# Sheet3.net
KiCad netlist of a schematic drawn in Altium Designer
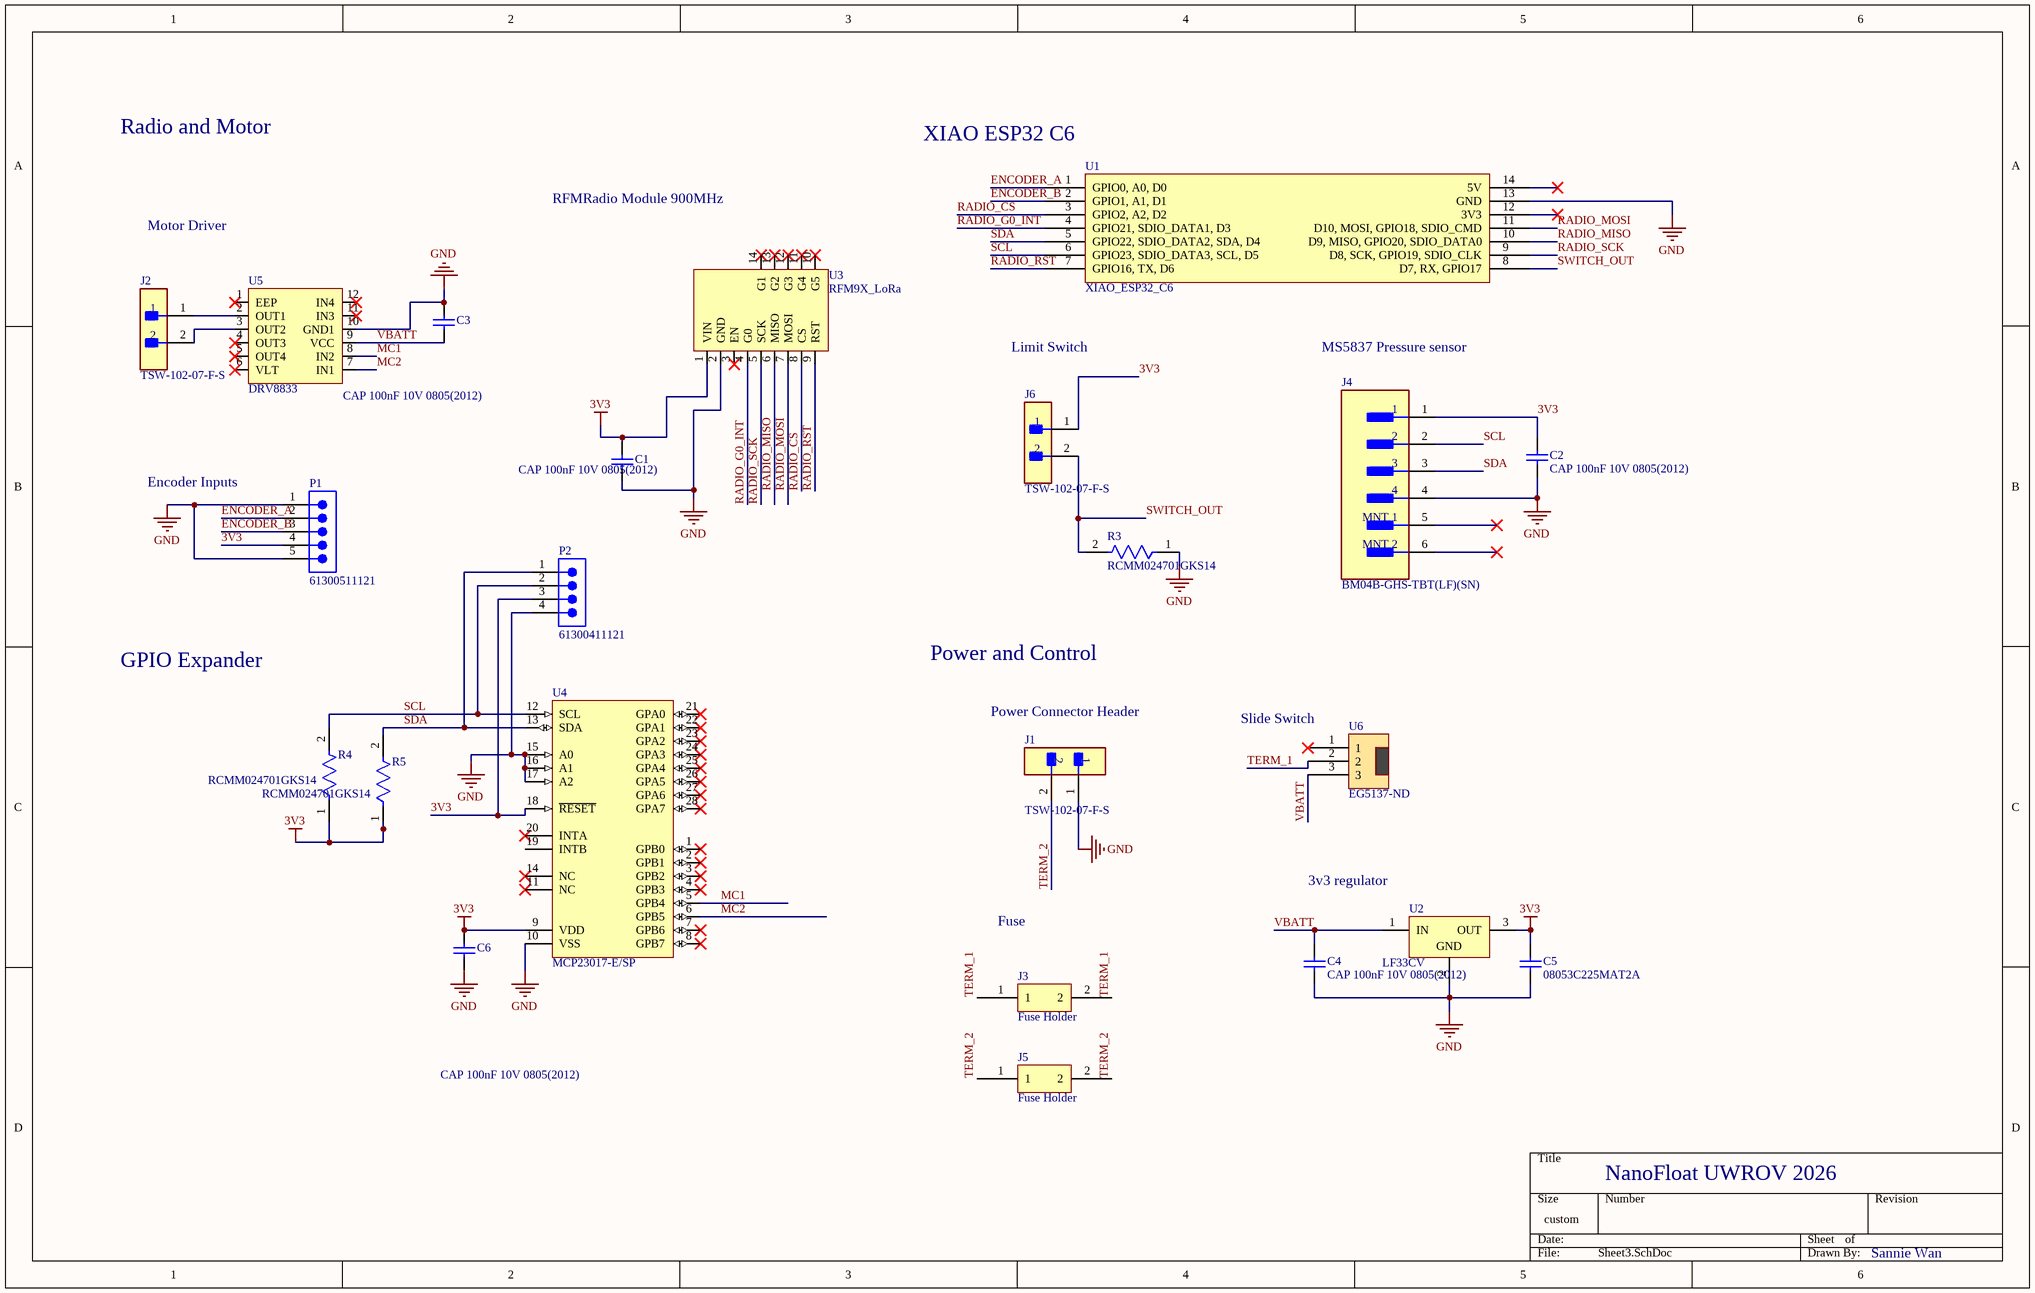
[diagram p0: Sheet3.SchDoc]

(export (version "E")
  (design (tool "Eeschema 10.0.6"))
  (components
    (comp (ref "C1")
      (value "CAP 100nF 10V 0805(2012)")
      (footprint "CAPC0805(2012)100_M")
      (description "CAP 100nF 10V ±5% 0805 (2012 Metric) Thickness 1mm SMD")
      (fields (field (name "TOLERANCE") "Â±5%"))
      (libsource (lib "Altium Content Vault") (part "CAP"))
    )
    (comp (ref "C2")
      (value "CAP 100nF 10V 0805(2012)")
      (footprint "CAPC0805(2012)100_M")
      (description "CAP 100nF 10V ±5% 0805 (2012 Metric) Thickness 1mm SMD")
      (fields (field (name "TOLERANCE") "Â±5%"))
      (libsource (lib "Altium Content Vault") (part "CAP"))
    )
    (comp (ref "C3")
      (value "CAP 100nF 10V 0805(2012)")
      (footprint "CAPC0805(2012)100_M")
      (description "CAP 100nF 10V ±5% 0805 (2012 Metric) Thickness 1mm SMD")
      (fields (field (name "TOLERANCE") "Â±5%"))
      (libsource (lib "Altium Content Vault") (part "CAP"))
    )
    (comp (ref "C4")
      (value "CAP 100nF 10V 0805(2012)")
      (footprint "CAPC0805(2012)100_M")
      (description "CAP 100nF 10V ±5% 0805 (2012 Metric) Thickness 1mm SMD")
      (fields (field (name "TOLERANCE") "Â±5%"))
      (libsource (lib "Altium Content Vault") (part "CAP"))
    )
    (comp (ref "C5")
      (value "08053C225MAT2A")
      (footprint "CAPC2013X152X50ML20T25")
      (fields (field (name "MANUFACTURER") "AVX Interconnect / Elco"))
      (libsource (lib "Altium Content Vault") (part "CAP"))
    )
    (comp (ref "C6")
      (value "CAP 100nF 10V 0805(2012)")
      (footprint "CAPC0805(2012)100_M")
      (description "CAP 100nF 10V ±5% 0805 (2012 Metric) Thickness 1mm SMD")
      (fields (field (name "TOLERANCE") "Â±5%"))
      (libsource (lib "Altium Content Vault") (part "CAP"))
    )
    (comp (ref "J1")
      (value "TSW-102-07-F-S")
      (footprint "FP-TSW-102-07-F-S-MFG")
      (description "CONN HEADER VERT 2POS 2.54MM")
      (libsource (lib "Altium Content Vault") (part "3bc925449376181038e59eaffc5286c"))
    )
    (comp (ref "J2")
      (value "TSW-102-07-F-S")
      (footprint "FP-TSW-102-07-F-S-MFG")
      (description "CONN HEADER VERT 2POS 2.54MM")
      (libsource (lib "") (part "3bc925449376181038e59eaffc5286c_1"))
    )
    (comp (ref "J3")
      (value "Fuse Holder")
      (footprint "FUSE_01110501Z")
      (libsource (lib "Schlib1") (part "Fuse_Holder"))
    )
    (comp (ref "J4")
      (value "BM04B-GHS-TBT(LF)(SN)")
      (footprint "FP-BM04B-GHS-TBT_LF_SN-MFG")
      (description "CONN HEADER SMD 4POS 1.25MM")
      (libsource (lib "Altium Content Vault") (part "8e3688c4b118bffc0dd9b7401e414ba"))
    )
    (comp (ref "J5")
      (value "Fuse Holder")
      (footprint "FUSE_01110501Z")
      (libsource (lib "Schlib1") (part "Fuse_Holder"))
    )
    (comp (ref "J6")
      (value "TSW-102-07-F-S")
      (footprint "FP-TSW-102-07-F-S-MFG")
      (description "CONN HEADER VERT 2POS 2.54MM")
      (libsource (lib "") (part "3bc925449376181038e59eaffc5286c_1"))
    )
    (comp (ref "P1")
      (value "61300511121")
      (footprint "61300511121")
      (description "THT Vertical Pin Header WR-PHD, Pitch 2.54 mm, Single Row, 5 pins")
      (libsource (lib "Altium Content Vault") (part "Header_Male_1R_05P"))
    )
    (comp (ref "P2")
      (value "61300411121")
      (footprint "61300411121")
      (description "THT Vertical Pin Header WR-PHD, Pitch 2.54 mm, Single Row, 4 pins")
      (libsource (lib "Altium Content Vault") (part "Header_Male_1R_04P"))
    )
    (comp (ref "R3")
      (value "RCMM024701GKS14")
      (footprint "FP-RCMM02-MFG")
      (description "RES 4.7K OHM 2% 1/2W AXIAL")
      (fields (field (name "TOLERANCE") "2%"))
      (libsource (lib "Altium Content Vault") (part "1029c3af85768c4190bb7ad29bc67b5"))
    )
    (comp (ref "R4")
      (value "RCMM024701GKS14")
      (footprint "FP-RCMM02-MFG")
      (description "RES 4.7K OHM 2% 1/2W AXIAL")
      (fields (field (name "TOLERANCE") "2%"))
      (libsource (lib "Altium Content Vault") (part "1029c3af85768c4190bb7ad29bc67b5"))
    )
    (comp (ref "R5")
      (value "RCMM024701GKS14")
      (footprint "FP-RCMM02-MFG")
      (description "RES 4.7K OHM 2% 1/2W AXIAL")
      (fields (field (name "TOLERANCE") "2%"))
      (libsource (lib "Altium Content Vault") (part "1029c3af85768c4190bb7ad29bc67b5"))
    )
    (comp (ref "U1")
      (value "XIAO_ESP32_C6")
      (footprint "MODULE_XIAO_ESP32C6")
      (description "seeed studio FCC ID:Z4T-XIAOESP32C6")
      (libsource (lib "Schlib1") (part "XIAO_ESP32_C6"))
    )
    (comp (ref "U2")
      (value "LF33CV")
      (footprint "TO220")
      (description "500mA, Very Low Drop (0.45V) Voltage Regulator, 3.3V, 3-Pin TO-220")
      (libsource (lib "Altium Content Vault") (part "PM-REG-L4940-SIL3"))
    )
    (comp (ref "U3")
      (value "RFM9X_LoRa")
      (footprint "RFM9X_LoRa")
      (libsource (lib "Schlib1") (part "RFM9X_LoRa"))
    )
    (comp (ref "U4")
      (value "MCP23017-E/SP")
      (footprint "SPDIP300-SP28")
      (description "16-Bit I/O Expander with Serial Interface, 28-Pin SPDIP, Extended Temperature")
      (libsource (lib "Altium Content Vault") (part "PR-BUSIC-MCP23017-28"))
    )
    (comp (ref "U5")
      (value "DRV8833")
      (footprint "DRV8833 Motor Driver")
      (description "Motor Driver 6.5V-45VDC In")
      (libsource (lib "Schlib1") (part "DRV8833"))
    )
    (comp (ref "U6")
      (value "EG5137-ND")
      (footprint "SW_500SSP1S2M2QEA")
      (description "Switch Slide ON None ON SPDT Extended Top Slide 5A 250VAC 28VDC PC Pins Thru-Hole")
      (fields
        (field (name "MANUFACTURER") "E-Switch")
        (field (name "MANUFACTURER PART NUMBER") "500SSP1S2M2QEA")
      )
      (libsource (lib "Schlib1") (part "500SSP1S2M2QEA"))
    )
  )
  (nets
    (net (code "1") (name "/ENCODER_A") (class "Default")
      (node (ref "P1") (pin "2") (pinfunction "2_2") (pintype "passive"))
      (node (ref "U1") (pin "1") (pinfunction "GPIO0,_A0,_D0_1") (pintype "passive"))
    )
    (net (code "2") (name "/ENCODER_B") (class "Default")
      (node (ref "P1") (pin "3") (pinfunction "3_3") (pintype "passive"))
      (node (ref "U1") (pin "2") (pinfunction "GPIO1,_A1,_D1_2") (pintype "passive"))
    )
    (net (code "3") (name "/MC1") (class "Default")
      (node (ref "U4") (pin "5") (pinfunction "GPB4_5") (pintype "bidirectional"))
      (node (ref "U5") (pin "8") (pinfunction "IN2_8") (pintype "passive"))
    )
    (net (code "4") (name "/MC2") (class "Default")
      (node (ref "U4") (pin "6") (pinfunction "GPB5_6") (pintype "bidirectional"))
      (node (ref "U5") (pin "7") (pinfunction "IN1_7") (pintype "passive"))
    )
    (net (code "5") (name "/RADIO_CS") (class "Default")
      (node (ref "U1") (pin "3") (pinfunction "GPIO2,_A2,_D2_3") (pintype "passive"))
      (node (ref "U3") (pin "8") (pinfunction "CS_8") (pintype "passive"))
    )
    (net (code "6") (name "/RADIO_G0_INT") (class "Default")
      (node (ref "U1") (pin "4") (pinfunction "GPIO21,_SDIO_DATA1,_D3_4") (pintype "passive"))
      (node (ref "U3") (pin "4") (pinfunction "G0_4") (pintype "passive"))
    )
    (net (code "7") (name "/RADIO_MISO") (class "Default")
      (node (ref "U1") (pin "10") (pinfunction "D9,_MISO,_GPIO20,_SDIO_DATA0_10") (pintype "passive"))
      (node (ref "U3") (pin "6") (pinfunction "MISO_6") (pintype "passive"))
    )
    (net (code "8") (name "/RADIO_MOSI") (class "Default")
      (node (ref "U1") (pin "11") (pinfunction "D10,_MOSI,_GPIO18,_SDIO_CMD_11") (pintype "passive"))
      (node (ref "U3") (pin "7") (pinfunction "MOSI_7") (pintype "passive"))
    )
    (net (code "9") (name "/RADIO_RST") (class "Default")
      (node (ref "U1") (pin "7") (pinfunction "GPIO16,_TX,_D6_7") (pintype "passive"))
      (node (ref "U3") (pin "9") (pinfunction "RST_9") (pintype "passive"))
    )
    (net (code "10") (name "/RADIO_SCK") (class "Default")
      (node (ref "U1") (pin "9") (pinfunction "D8,_SCK,_GPIO19,_SDIO_CLK_9") (pintype "passive"))
      (node (ref "U3") (pin "5") (pinfunction "SCK_5") (pintype "passive"))
    )
    (net (code "11") (name "/SCL") (class "Default")
      (node (ref "J4") (pin "2") (pinfunction "2_2") (pintype "passive"))
      (node (ref "P2") (pin "2") (pinfunction "2_2") (pintype "passive"))
      (node (ref "R4") (pin "2") (pinfunction "2_2") (pintype "passive"))
      (node (ref "U1") (pin "6") (pinfunction "GPIO23,_SDIO_DATA3,_SCL,_D5_6") (pintype "passive"))
      (node (ref "U4") (pin "12") (pinfunction "SCL_12") (pintype "input"))
    )
    (net (code "12") (name "/SDA") (class "Default")
      (node (ref "J4") (pin "3") (pinfunction "3_3") (pintype "passive"))
      (node (ref "P2") (pin "1") (pinfunction "1_1") (pintype "passive"))
      (node (ref "R5") (pin "2") (pinfunction "2_2") (pintype "passive"))
      (node (ref "U1") (pin "5") (pinfunction "GPIO22,_SDIO_DATA2,_SDA,_D4_5") (pintype "passive"))
      (node (ref "U4") (pin "13") (pinfunction "SDA_13") (pintype "bidirectional"))
    )
    (net (code "13") (name "/SWITCH_OUT") (class "Default")
      (node (ref "J6") (pin "2") (pinfunction "2_2") (pintype "passive"))
      (node (ref "R3") (pin "2") (pinfunction "2_2") (pintype "passive"))
      (node (ref "U1") (pin "8") (pinfunction "D7,_RX,_GPIO17_8") (pintype "passive"))
    )
    (net (code "14") (name "/TERM_1") (class "Default")
      (node (ref "J3") (pin "1") (pinfunction "1_1") (pintype "passive"))
      (node (ref "J3") (pin "2") (pinfunction "2_2") (pintype "passive"))
      (node (ref "U6") (pin "2") (pinfunction "2_2") (pintype "passive"))
    )
    (net (code "15") (name "/TERM_2") (class "Default")
      (node (ref "J1") (pin "2") (pinfunction "2_2") (pintype "passive"))
      (node (ref "J5") (pin "1") (pinfunction "1_1") (pintype "passive"))
      (node (ref "J5") (pin "2") (pinfunction "2_2") (pintype "passive"))
    )
    (net (code "16") (name "/VBATT") (class "Default")
      (node (ref "C3") (pin "1") (pinfunction "1_1") (pintype "passive"))
      (node (ref "C4") (pin "2") (pinfunction "2_2") (pintype "passive"))
      (node (ref "U2") (pin "1") (pinfunction "IN_1") (pintype "power_in"))
      (node (ref "U5") (pin "9") (pinfunction "VCC_9") (pintype "passive"))
      (node (ref "U6") (pin "3") (pinfunction "3_3") (pintype "passive"))
    )
    (net (code "17") (name "3V3") (class "Default")
      (node (ref "C1") (pin "2") (pinfunction "2_2") (pintype "passive"))
      (node (ref "C2") (pin "2") (pinfunction "2_2") (pintype "passive"))
      (node (ref "C5") (pin "2") (pinfunction "2_2") (pintype "passive"))
      (node (ref "C6") (pin "2") (pinfunction "2_2") (pintype "passive"))
      (node (ref "J4") (pin "1") (pinfunction "1_1") (pintype "passive"))
      (node (ref "J6") (pin "1") (pinfunction "1_1") (pintype "passive"))
      (node (ref "P1") (pin "4") (pinfunction "4_4") (pintype "passive"))
      (node (ref "P2") (pin "3") (pinfunction "3_3") (pintype "passive"))
      (node (ref "R4") (pin "1") (pinfunction "1_1") (pintype "passive"))
      (node (ref "R5") (pin "1") (pinfunction "1_1") (pintype "passive"))
      (node (ref "U2") (pin "3") (pinfunction "OUT_3") (pintype "power_in"))
      (node (ref "U3") (pin "1") (pinfunction "VIN_1") (pintype "passive"))
      (node (ref "U4") (pin "18") (pinfunction "~{RESET}_18") (pintype "input"))
      (node (ref "U4") (pin "9") (pinfunction "VDD_9") (pintype "power_in"))
    )
    (net (code "18") (name "GND") (class "Default")
      (node (ref "C1") (pin "1") (pinfunction "1_1") (pintype "passive"))
      (node (ref "C2") (pin "1") (pinfunction "1_1") (pintype "passive"))
      (node (ref "C3") (pin "2") (pinfunction "2_2") (pintype "passive"))
      (node (ref "C4") (pin "1") (pinfunction "1_1") (pintype "passive"))
      (node (ref "C5") (pin "1") (pinfunction "1_1") (pintype "passive"))
      (node (ref "C6") (pin "1") (pinfunction "1_1") (pintype "passive"))
      (node (ref "J1") (pin "1") (pinfunction "1_1") (pintype "passive"))
      (node (ref "J4") (pin "4") (pinfunction "4_4") (pintype "passive"))
      (node (ref "P1") (pin "1") (pinfunction "1_1") (pintype "passive"))
      (node (ref "P1") (pin "5") (pinfunction "5_5") (pintype "passive"))
      (node (ref "P2") (pin "4") (pinfunction "4_4") (pintype "passive"))
      (node (ref "R3") (pin "1") (pinfunction "1_1") (pintype "passive"))
      (node (ref "U1") (pin "13") (pinfunction "GND_13") (pintype "passive"))
      (node (ref "U2") (pin "2") (pinfunction "GND_2") (pintype "power_in"))
      (node (ref "U3") (pin "2") (pinfunction "GND_2") (pintype "passive"))
      (node (ref "U4") (pin "10") (pinfunction "VSS_10") (pintype "power_in"))
      (node (ref "U4") (pin "15") (pinfunction "A0_15") (pintype "input"))
      (node (ref "U4") (pin "16") (pinfunction "A1_16") (pintype "input"))
      (node (ref "U4") (pin "17") (pinfunction "A2_17") (pintype "input"))
      (node (ref "U5") (pin "10") (pinfunction "GND1_10") (pintype "passive"))
    )
    (net (code "19") (name "Net-(U5-OUT1)") (class "Default")
      (node (ref "J2") (pin "1") (pinfunction "1_1") (pintype "passive"))
      (node (ref "U5") (pin "2") (pinfunction "OUT1_2") (pintype "passive"))
    )
    (net (code "20") (name "Net-(U5-OUT2)") (class "Default")
      (node (ref "J2") (pin "2") (pinfunction "2_2") (pintype "passive"))
      (node (ref "U5") (pin "3") (pinfunction "OUT2_3") (pintype "passive"))
    )
    (net (code "21") (name "unconnected-(J4-MNT_1-Pad5)") (class "Default")
      (node (ref "J4") (pin "5") (pinfunction "MNT_1_5") (pintype "passive+no_connect"))
    )
    (net (code "22") (name "unconnected-(J4-MNT_2-Pad6)") (class "Default")
      (node (ref "J4") (pin "6") (pinfunction "MNT_2_6") (pintype "passive+no_connect"))
    )
    (net (code "23") (name "unconnected-(U1-3V3-Pad12)") (class "Default")
      (node (ref "U1") (pin "12") (pinfunction "3V3_12") (pintype "passive+no_connect"))
    )
    (net (code "24") (name "unconnected-(U1-5V-Pad14)") (class "Default")
      (node (ref "U1") (pin "14") (pinfunction "5V_14") (pintype "passive+no_connect"))
    )
    (net (code "25") (name "unconnected-(U3-EN-Pad3)") (class "Default")
      (node (ref "U3") (pin "3") (pinfunction "EN_3") (pintype "passive+no_connect"))
    )
    (net (code "26") (name "unconnected-(U3-G1-Pad14)") (class "Default")
      (node (ref "U3") (pin "14") (pinfunction "G1_14") (pintype "passive+no_connect"))
    )
    (net (code "27") (name "unconnected-(U3-G2-Pad13)") (class "Default")
      (node (ref "U3") (pin "13") (pinfunction "G2_13") (pintype "passive+no_connect"))
    )
    (net (code "28") (name "unconnected-(U3-G3-Pad12)") (class "Default")
      (node (ref "U3") (pin "12") (pinfunction "G3_12") (pintype "passive+no_connect"))
    )
    (net (code "29") (name "unconnected-(U3-G4-Pad11)") (class "Default")
      (node (ref "U3") (pin "11") (pinfunction "G4_11") (pintype "passive+no_connect"))
    )
    (net (code "30") (name "unconnected-(U3-G5-Pad10)") (class "Default")
      (node (ref "U3") (pin "10") (pinfunction "G5_10") (pintype "passive+no_connect"))
    )
    (net (code "31") (name "unconnected-(U4-GPA0-Pad21)") (class "Default")
      (node (ref "U4") (pin "21") (pinfunction "GPA0_21") (pintype "bidirectional+no_connect"))
    )
    (net (code "32") (name "unconnected-(U4-GPA1-Pad22)") (class "Default")
      (node (ref "U4") (pin "22") (pinfunction "GPA1_22") (pintype "bidirectional+no_connect"))
    )
    (net (code "33") (name "unconnected-(U4-GPA2-Pad23)") (class "Default")
      (node (ref "U4") (pin "23") (pinfunction "GPA2_23") (pintype "bidirectional+no_connect"))
    )
    (net (code "34") (name "unconnected-(U4-GPA3-Pad24)") (class "Default")
      (node (ref "U4") (pin "24") (pinfunction "GPA3_24") (pintype "bidirectional+no_connect"))
    )
    (net (code "35") (name "unconnected-(U4-GPA4-Pad25)") (class "Default")
      (node (ref "U4") (pin "25") (pinfunction "GPA4_25") (pintype "bidirectional+no_connect"))
    )
    (net (code "36") (name "unconnected-(U4-GPA5-Pad26)") (class "Default")
      (node (ref "U4") (pin "26") (pinfunction "GPA5_26") (pintype "bidirectional+no_connect"))
    )
    (net (code "37") (name "unconnected-(U4-GPA6-Pad27)") (class "Default")
      (node (ref "U4") (pin "27") (pinfunction "GPA6_27") (pintype "bidirectional+no_connect"))
    )
    (net (code "38") (name "unconnected-(U4-GPA7-Pad28)") (class "Default")
      (node (ref "U4") (pin "28") (pinfunction "GPA7_28") (pintype "bidirectional+no_connect"))
    )
    (net (code "39") (name "unconnected-(U4-GPB0-Pad1)") (class "Default")
      (node (ref "U4") (pin "1") (pinfunction "GPB0_1") (pintype "bidirectional+no_connect"))
    )
    (net (code "40") (name "unconnected-(U4-GPB1-Pad2)") (class "Default")
      (node (ref "U4") (pin "2") (pinfunction "GPB1_2") (pintype "bidirectional+no_connect"))
    )
    (net (code "41") (name "unconnected-(U4-GPB2-Pad3)") (class "Default")
      (node (ref "U4") (pin "3") (pinfunction "GPB2_3") (pintype "bidirectional+no_connect"))
    )
    (net (code "42") (name "unconnected-(U4-GPB3-Pad4)") (class "Default")
      (node (ref "U4") (pin "4") (pinfunction "GPB3_4") (pintype "bidirectional+no_connect"))
    )
    (net (code "43") (name "unconnected-(U4-GPB6-Pad7)") (class "Default")
      (node (ref "U4") (pin "7") (pinfunction "GPB6_7") (pintype "bidirectional+no_connect"))
    )
    (net (code "44") (name "unconnected-(U4-GPB7-Pad8)") (class "Default")
      (node (ref "U4") (pin "8") (pinfunction "GPB7_8") (pintype "bidirectional+no_connect"))
    )
    (net (code "45") (name "unconnected-(U4-INTA-Pad20)") (class "Default")
      (node (ref "U4") (pin "20") (pinfunction "INTA_20") (pintype "open_collector+no_connect"))
    )
    (net (code "46") (name "unconnected-(U4-INTB-Pad19)") (class "Default")
      (node (ref "U4") (pin "19") (pinfunction "INTB_19") (pintype "open_collector"))
    )
    (net (code "47") (name "unconnected-(U4-NC-Pad11)") (class "Default")
      (node (ref "U4") (pin "11") (pinfunction "NC_11") (pintype "passive+no_connect"))
    )
    (net (code "48") (name "unconnected-(U4-NC-Pad14)") (class "Default")
      (node (ref "U4") (pin "14") (pinfunction "NC_14") (pintype "passive+no_connect"))
    )
    (net (code "49") (name "unconnected-(U5-EEP-Pad1)") (class "Default")
      (node (ref "U5") (pin "1") (pinfunction "EEP_1") (pintype "passive+no_connect"))
    )
    (net (code "50") (name "unconnected-(U5-IN3-Pad11)") (class "Default")
      (node (ref "U5") (pin "11") (pinfunction "IN3_11") (pintype "passive+no_connect"))
    )
    (net (code "51") (name "unconnected-(U5-IN4-Pad12)") (class "Default")
      (node (ref "U5") (pin "12") (pinfunction "IN4_12") (pintype "passive+no_connect"))
    )
    (net (code "52") (name "unconnected-(U5-OUT3-Pad4)") (class "Default")
      (node (ref "U5") (pin "4") (pinfunction "OUT3_4") (pintype "passive+no_connect"))
    )
    (net (code "53") (name "unconnected-(U5-OUT4-Pad5)") (class "Default")
      (node (ref "U5") (pin "5") (pinfunction "OUT4_5") (pintype "passive+no_connect"))
    )
    (net (code "54") (name "unconnected-(U5-VLT-Pad6)") (class "Default")
      (node (ref "U5") (pin "6") (pinfunction "VLT_6") (pintype "passive+no_connect"))
    )
    (net (code "55") (name "unconnected-(U6-Pad1)") (class "Default")
      (node (ref "U6") (pin "1") (pinfunction "1_1") (pintype "passive+no_connect"))
    )
  )
)
